# m12can.net
KiCad netlist of a schematic drawn in Altium Designer
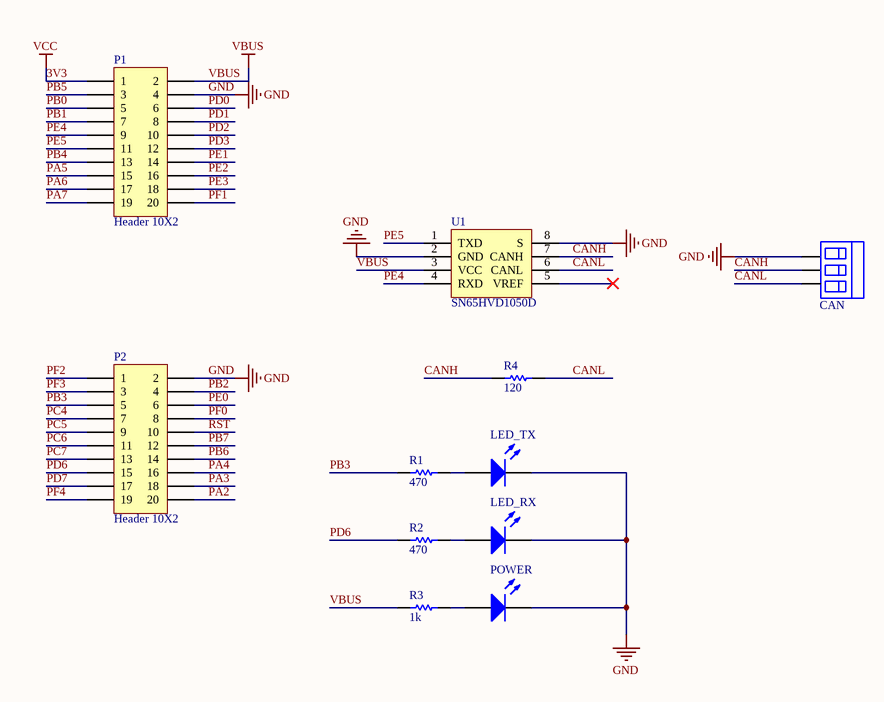
[diagram p0: m12can.SchDoc]

(export (version "E")
  (design (tool "Eeschema 10.0.6"))
  (components
    (comp (ref "CAN")
      (value "CAN")
      (footprint "MKDSN_3RMI")
      (libsource (lib "战舰STM32开发板底板封装库") (part "HEAD3"))
    )
    (comp (ref "LED_RX")
      (value "LED2")
      (footprint "LED_0603_RED")
      (description "Typical RED, GREEN, YELLOW, AMBER GaAs LED")
      (fields (field (name "PUBLISHER") "Altium Limited"))
      (libsource (lib "Miscellaneous Devices") (part "LED2"))
    )
    (comp (ref "LED_TX")
      (value "LED2")
      (footprint "LED_0603_RED")
      (description "Typical RED, GREEN, YELLOW, AMBER GaAs LED")
      (fields (field (name "PUBLISHER") "Altium Limited"))
      (libsource (lib "Miscellaneous Devices") (part "LED2"))
    )
    (comp (ref "P1")
      (value "Header 10X2")
      (footprint "HDR2X10")
      (description "Header, 10-Pin, Dual row")
      (fields (field (name "PUBLISHER") "Altium Limited"))
      (libsource (lib "Miscellaneous Connectors") (part "Header 10X2"))
    )
    (comp (ref "P2")
      (value "Header 10X2")
      (footprint "HDR2X10")
      (description "Header, 10-Pin, Dual row")
      (fields (field (name "PUBLISHER") "Altium Limited"))
      (libsource (lib "Miscellaneous Connectors") (part "Header 10X2"))
    )
    (comp (ref "POWER")
      (value "LED2")
      (footprint "LED_0603_RED")
      (description "Typical RED, GREEN, YELLOW, AMBER GaAs LED")
      (fields (field (name "PUBLISHER") "Altium Limited"))
      (libsource (lib "Miscellaneous Devices") (part "LED2"))
    )
    (comp (ref "R1")
      (value "470")
      (footprint "RES_0603")
      (description "Resistor")
      (fields (field (name "Comment") "Res1") (field (name "PUBLISHER") "Altium Limited"))
      (libsource (lib "Miscellaneous Devices") (part "Res1"))
    )
    (comp (ref "R2")
      (value "470")
      (footprint "RES_0603")
      (description "Resistor")
      (fields (field (name "Comment") "Res1") (field (name "PUBLISHER") "Altium Limited"))
      (libsource (lib "Miscellaneous Devices") (part "Res1"))
    )
    (comp (ref "R3")
      (value "1k")
      (footprint "RES_0603")
      (description "Resistor")
      (fields (field (name "Comment") "Res1") (field (name "PUBLISHER") "Altium Limited"))
      (libsource (lib "Miscellaneous Devices") (part "Res1"))
    )
    (comp (ref "R4")
      (value "120")
      (footprint "RES_0603")
      (description "Resistor")
      (fields (field (name "Comment") "Res1") (field (name "PUBLISHER") "Altium Limited"))
      (libsource (lib "Miscellaneous Devices") (part "Res1"))
    )
    (comp (ref "U1")
      (value "SN65HVD1050D")
      (footprint "SOIC-8")
      (description "EMC OPTIMIZED CAN TRANSCEIVER,SN65HVD1050D")
      (libsource (lib "m12") (part "SN65HVD1050D"))
    )
  )
  (nets
    (net (code "1") (name "/CANH") (class "Default")
      (node (ref "CAN") (pin "2") (pinfunction "2_2") (pintype "passive"))
      (node (ref "R4") (pin "1") (pinfunction "1_1") (pintype "passive"))
      (node (ref "U1") (pin "7") (pinfunction "CANH_7") (pintype "passive"))
    )
    (net (code "2") (name "/CANL") (class "Default")
      (node (ref "CAN") (pin "3") (pinfunction "3_3") (pintype "passive"))
      (node (ref "R4") (pin "2") (pinfunction "2_2") (pintype "passive"))
      (node (ref "U1") (pin "6") (pinfunction "CANL_6") (pintype "passive"))
    )
    (net (code "3") (name "/PA2") (class "Default")
      (node (ref "P2") (pin "20") (pinfunction "20_20") (pintype "passive"))
    )
    (net (code "4") (name "/PA3") (class "Default")
      (node (ref "P2") (pin "18") (pinfunction "18_18") (pintype "passive"))
    )
    (net (code "5") (name "/PA4") (class "Default")
      (node (ref "P2") (pin "16") (pinfunction "16_16") (pintype "passive"))
    )
    (net (code "6") (name "/PA5") (class "Default")
      (node (ref "P1") (pin "15") (pinfunction "15_15") (pintype "passive"))
    )
    (net (code "7") (name "/PA6") (class "Default")
      (node (ref "P1") (pin "17") (pinfunction "17_17") (pintype "passive"))
    )
    (net (code "8") (name "/PA7") (class "Default")
      (node (ref "P1") (pin "19") (pinfunction "19_19") (pintype "passive"))
    )
    (net (code "9") (name "/PB0") (class "Default")
      (node (ref "P1") (pin "5") (pinfunction "5_5") (pintype "passive"))
    )
    (net (code "10") (name "/PB1") (class "Default")
      (node (ref "P1") (pin "7") (pinfunction "7_7") (pintype "passive"))
    )
    (net (code "11") (name "/PB2") (class "Default")
      (node (ref "P2") (pin "4") (pinfunction "4_4") (pintype "passive"))
    )
    (net (code "12") (name "/PB3") (class "Default")
      (node (ref "P2") (pin "5") (pinfunction "5_5") (pintype "passive"))
      (node (ref "R1") (pin "1") (pinfunction "1_1") (pintype "passive"))
    )
    (net (code "13") (name "/PB4") (class "Default")
      (node (ref "P1") (pin "13") (pinfunction "13_13") (pintype "passive"))
    )
    (net (code "14") (name "/PB5") (class "Default")
      (node (ref "P1") (pin "3") (pinfunction "3_3") (pintype "passive"))
    )
    (net (code "15") (name "/PB6") (class "Default")
      (node (ref "P2") (pin "14") (pinfunction "14_14") (pintype "passive"))
    )
    (net (code "16") (name "/PB7") (class "Default")
      (node (ref "P2") (pin "12") (pinfunction "12_12") (pintype "passive"))
    )
    (net (code "17") (name "/PC4") (class "Default")
      (node (ref "P2") (pin "7") (pinfunction "7_7") (pintype "passive"))
    )
    (net (code "18") (name "/PC5") (class "Default")
      (node (ref "P2") (pin "9") (pinfunction "9_9") (pintype "passive"))
    )
    (net (code "19") (name "/PC6") (class "Default")
      (node (ref "P2") (pin "11") (pinfunction "11_11") (pintype "passive"))
    )
    (net (code "20") (name "/PC7") (class "Default")
      (node (ref "P2") (pin "13") (pinfunction "13_13") (pintype "passive"))
    )
    (net (code "21") (name "/PD0") (class "Default")
      (node (ref "P1") (pin "6") (pinfunction "6_6") (pintype "passive"))
    )
    (net (code "22") (name "/PD1") (class "Default")
      (node (ref "P1") (pin "8") (pinfunction "8_8") (pintype "passive"))
    )
    (net (code "23") (name "/PD2") (class "Default")
      (node (ref "P1") (pin "10") (pinfunction "10_10") (pintype "passive"))
    )
    (net (code "24") (name "/PD3") (class "Default")
      (node (ref "P1") (pin "12") (pinfunction "12_12") (pintype "passive"))
    )
    (net (code "25") (name "/PD6") (class "Default")
      (node (ref "P2") (pin "15") (pinfunction "15_15") (pintype "passive"))
      (node (ref "R2") (pin "1") (pinfunction "1_1") (pintype "passive"))
    )
    (net (code "26") (name "/PD7") (class "Default")
      (node (ref "P2") (pin "17") (pinfunction "17_17") (pintype "passive"))
    )
    (net (code "27") (name "/PE0") (class "Default")
      (node (ref "P2") (pin "6") (pinfunction "6_6") (pintype "passive"))
    )
    (net (code "28") (name "/PE1") (class "Default")
      (node (ref "P1") (pin "14") (pinfunction "14_14") (pintype "passive"))
    )
    (net (code "29") (name "/PE2") (class "Default")
      (node (ref "P1") (pin "16") (pinfunction "16_16") (pintype "passive"))
    )
    (net (code "30") (name "/PE3") (class "Default")
      (node (ref "P1") (pin "18") (pinfunction "18_18") (pintype "passive"))
    )
    (net (code "31") (name "/PE4") (class "Default")
      (node (ref "P1") (pin "9") (pinfunction "9_9") (pintype "passive"))
      (node (ref "U1") (pin "4") (pinfunction "RXD_4") (pintype "passive"))
    )
    (net (code "32") (name "/PE5") (class "Default")
      (node (ref "P1") (pin "11") (pinfunction "11_11") (pintype "passive"))
      (node (ref "U1") (pin "1") (pinfunction "TXD_1") (pintype "passive"))
    )
    (net (code "33") (name "/PF0") (class "Default")
      (node (ref "P2") (pin "8") (pinfunction "8_8") (pintype "passive"))
    )
    (net (code "34") (name "/PF1") (class "Default")
      (node (ref "P1") (pin "20") (pinfunction "20_20") (pintype "passive"))
    )
    (net (code "35") (name "/PF2") (class "Default")
      (node (ref "P2") (pin "1") (pinfunction "1_1") (pintype "passive"))
    )
    (net (code "36") (name "/PF3") (class "Default")
      (node (ref "P2") (pin "3") (pinfunction "3_3") (pintype "passive"))
    )
    (net (code "37") (name "/PF4") (class "Default")
      (node (ref "P2") (pin "19") (pinfunction "19_19") (pintype "passive"))
    )
    (net (code "38") (name "/RST") (class "Default")
      (node (ref "P2") (pin "10") (pinfunction "10_10") (pintype "passive"))
    )
    (net (code "39") (name "GND") (class "Default")
      (node (ref "CAN") (pin "1") (pinfunction "1_1") (pintype "passive"))
      (node (ref "LED_RX") (pin "2") (pinfunction "K_2") (pintype "passive"))
      (node (ref "LED_TX") (pin "2") (pinfunction "K_2") (pintype "passive"))
      (node (ref "P1") (pin "4") (pinfunction "4_4") (pintype "passive"))
      (node (ref "P2") (pin "2") (pinfunction "2_2") (pintype "passive"))
      (node (ref "POWER") (pin "2") (pinfunction "K_2") (pintype "passive"))
      (node (ref "U1") (pin "2") (pinfunction "GND_2") (pintype "passive"))
      (node (ref "U1") (pin "8") (pinfunction "S_8") (pintype "passive"))
    )
    (net (code "40") (name "Net-(LED_RX-A)") (class "Default")
      (node (ref "LED_RX") (pin "1") (pinfunction "A_1") (pintype "passive"))
      (node (ref "R2") (pin "2") (pinfunction "2_2") (pintype "passive"))
    )
    (net (code "41") (name "Net-(LED_TX-A)") (class "Default")
      (node (ref "LED_TX") (pin "1") (pinfunction "A_1") (pintype "passive"))
      (node (ref "R1") (pin "2") (pinfunction "2_2") (pintype "passive"))
    )
    (net (code "42") (name "Net-(POWER-A)") (class "Default")
      (node (ref "POWER") (pin "1") (pinfunction "A_1") (pintype "passive"))
      (node (ref "R3") (pin "2") (pinfunction "2_2") (pintype "passive"))
    )
    (net (code "43") (name "VBUS") (class "Default")
      (node (ref "P1") (pin "2") (pinfunction "2_2") (pintype "passive"))
      (node (ref "R3") (pin "1") (pinfunction "1_1") (pintype "passive"))
      (node (ref "U1") (pin "3") (pinfunction "VCC_3") (pintype "passive"))
    )
    (net (code "44") (name "VCC") (class "Default")
      (node (ref "P1") (pin "1") (pinfunction "1_1") (pintype "passive"))
    )
    (net (code "45") (name "unconnected-(U1-VREF-Pad5)") (class "Default")
      (node (ref "U1") (pin "5") (pinfunction "VREF_5") (pintype "passive+no_connect"))
    )
  )
)
